# Adaptor_PCB.net
KiCad netlist of a schematic drawn in Altium Designer
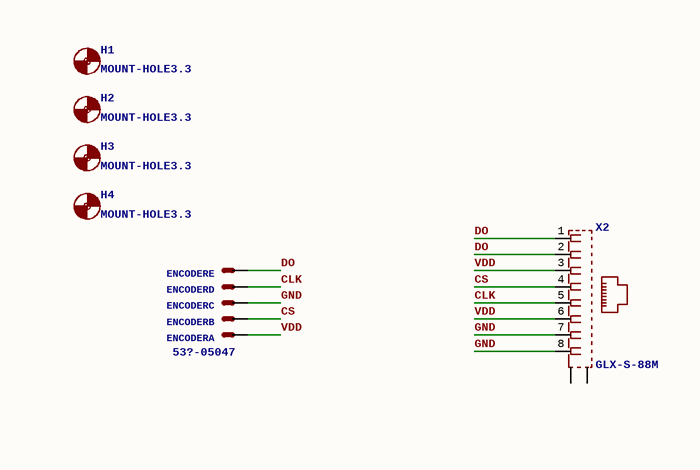
[diagram p0: Adaptor PCB.SchDoc]

(export (version "E")
  (design (tool "Eeschema 10.0.6"))
  (components
    (comp (ref "ENCODER")
      (value "53?-05047")
      (footprint "53047-05")
      (description "CONNECTORwire to board 1.25 mm (.049 inch) pitch header")
      (fields (field (name "MF") "MOLEX") (field (name "MPN") "53047-0510"))
      (libsource (lib "con-molex") (part "53?-05047"))
    )
    (comp (ref "H1")
      (value "MOUNT-HOLE3.3")
      (footprint "3,3")
      (description "MOUNTING HOLE with drill center marker")
      (libsource (lib "holes") (part "MOUNT-HOLE3.3"))
    )
    (comp (ref "H2")
      (value "MOUNT-HOLE3.3")
      (footprint "3,3")
      (description "MOUNTING HOLE with drill center marker")
      (libsource (lib "holes") (part "MOUNT-HOLE3.3"))
    )
    (comp (ref "H3")
      (value "MOUNT-HOLE3.3")
      (footprint "3,3")
      (description "MOUNTING HOLE with drill center marker")
      (libsource (lib "holes") (part "MOUNT-HOLE3.3"))
    )
    (comp (ref "H4")
      (value "MOUNT-HOLE3.3")
      (footprint "3,3")
      (description "MOUNTING HOLE with drill center marker")
      (libsource (lib "holes") (part "MOUNT-HOLE3.3"))
    )
    (comp (ref "X2")
      (value "GLX-S-88M")
      (footprint "GLX-S-88M")
      (description "Mod. Jack, Right Angle, 8 posiotion, 8 contatcs RJ45Source: GLX-S-88M.pdf")
      (fields (field (name "LIBRARYNAME") "con-kycon"))
      (libsource (lib "con-kycon") (part "GLX-S-88M"))
    )
  )
  (nets
    (net (code "1") (name "/CLK") (class "Default")
      (node (ref "ENCODER") (pin "4") (pinfunction "S_4") (pintype "passive"))
      (node (ref "X2") (pin "5") (pinfunction "5_5") (pintype "passive"))
    )
    (net (code "2") (name "/CS") (class "Default")
      (node (ref "ENCODER") (pin "2") (pinfunction "S_2") (pintype "passive"))
      (node (ref "X2") (pin "4") (pinfunction "4_4") (pintype "passive"))
    )
    (net (code "3") (name "/DO") (class "Default")
      (node (ref "ENCODER") (pin "5") (pinfunction "S_5") (pintype "passive"))
      (node (ref "X2") (pin "1") (pinfunction "1_1") (pintype "passive"))
      (node (ref "X2") (pin "2") (pinfunction "2_2") (pintype "passive"))
    )
    (net (code "4") (name "/GND") (class "Default")
      (node (ref "ENCODER") (pin "3") (pinfunction "S_3") (pintype "passive"))
      (node (ref "X2") (pin "7") (pinfunction "7_7") (pintype "passive"))
      (node (ref "X2") (pin "8") (pinfunction "8_8") (pintype "passive"))
    )
    (net (code "5") (name "/VDD") (class "Default")
      (node (ref "ENCODER") (pin "1") (pinfunction "S_1") (pintype "passive"))
      (node (ref "X2") (pin "3") (pinfunction "3_3") (pintype "passive"))
      (node (ref "X2") (pin "6") (pinfunction "6_6") (pintype "passive"))
    )
    (net (code "6") (name "unconnected-(X2-PadS1)") (class "Default")
      (node (ref "X2") (pin "S1") (pinfunction "S1_S1") (pintype "passive"))
    )
    (net (code "7") (name "unconnected-(X2-PadS2)") (class "Default")
      (node (ref "X2") (pin "S2") (pinfunction "S2_S2") (pintype "passive"))
    )
  )
)
